# BareBones-Arduino.net
KiCad netlist of a schematic drawn in EAGLE
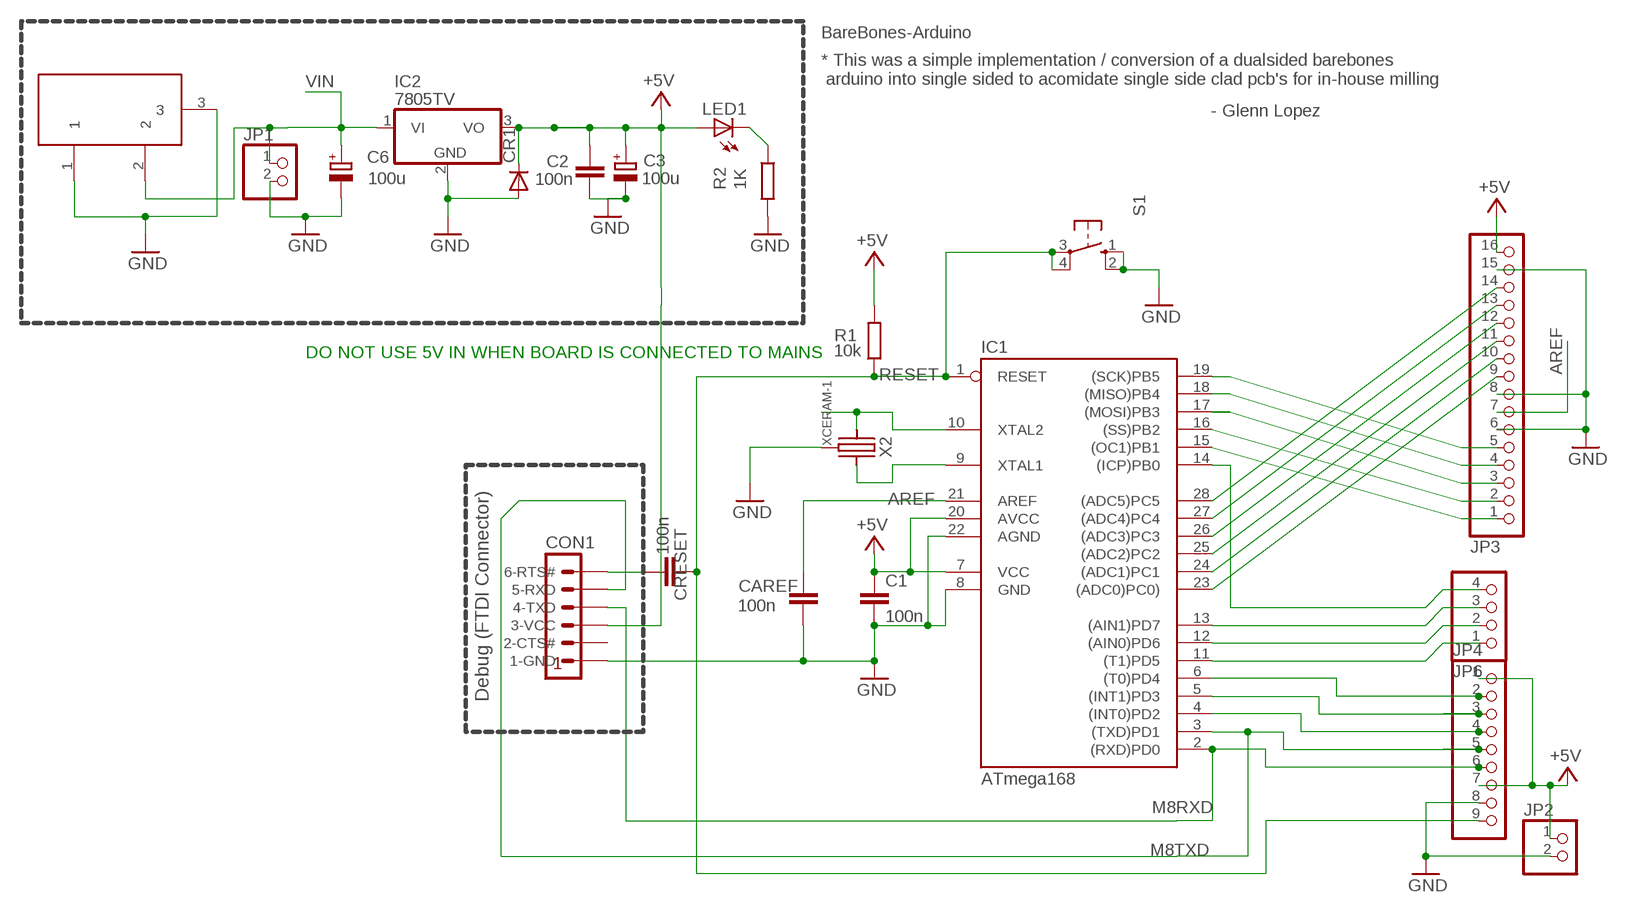
[diagram p0: schematic, sheet 1]

(export (version "E")
  (design (tool "Eeschema 10.0.6"))
  (components
    (comp (ref "C1")
      (value "100n")
      (footprint "eagle-import:C025-025X050")
      (libsource (lib "eagle-import") (part "C-EU025-025X050"))
    )
    (comp (ref "C2")
      (value "100n")
      (footprint "eagle-import:C1206K")
      (libsource (lib "eagle-import") (part "C-EUC1206K"))
    )
    (comp (ref "C3")
      (value "100u")
      (footprint "eagle-import:E2,5-7")
      (libsource (lib "eagle-import") (part "CPOL-EUE2.5-7"))
    )
    (comp (ref "C6")
      (value "100u")
      (footprint "eagle-import:E2,5-7")
      (libsource (lib "eagle-import") (part "CPOL-EUE2.5-7"))
    )
    (comp (ref "CAREF")
      (value "100n")
      (footprint "eagle-import:C1206K")
      (libsource (lib "eagle-import") (part "C-EUC1206K"))
    )
    (comp (ref "CON1")
      (value "FTDI-TTL232R")
      (footprint "eagle-import:MA06-1")
      (libsource (lib "eagle-import") (part "FTDI-TTL232R"))
    )
    (comp (ref "CR1")
      (value "DIODE-1ARECT-2V")
      (footprint "eagle-import:DO41-2V")
      (libsource (lib "eagle-import") (part "DIODE-1ARECT-2V"))
    )
    (comp (ref "CRESET")
      (value "100n")
      (footprint "eagle-import:C025-025X050")
      (libsource (lib "eagle-import") (part "C-EU025-025X050"))
    )
    (comp (ref "IC1")
      (value "ATmega168")
      (footprint "eagle-import:DIL28-3")
      (libsource (lib "eagle-import") (part "AT90S4433P"))
    )
    (comp (ref "IC2")
      (value "7805TV")
      (footprint "eagle-import:TO220V")
      (libsource (lib "eagle-import") (part "78TV05"))
    )
    (comp (ref "JP1")
      (value "PINHD-1X2")
      (footprint "eagle-import:1X02")
      (libsource (lib "eagle-import") (part "PINHD-1X2"))
    )
    (comp (ref "JP2")
      (value "PINHD-1X2")
      (footprint "eagle-import:1X02")
      (libsource (lib "eagle-import") (part "PINHD-1X2"))
    )
    (comp (ref "JP3")
      (value "PINHD-1X16-BARE")
      (footprint "eagle-import:1X16-BARE")
      (libsource (lib "eagle-import") (part "PINHD-1X16-BARE"))
    )
    (comp (ref "JP4")
      (value "PINHD-1X9-BARE")
      (footprint "eagle-import:1X09-BARE")
      (libsource (lib "eagle-import") (part "PINHD-1X9-BARE"))
    )
    (comp (ref "JP6")
      (value "PINHD-1X4-BARE")
      (footprint "eagle-import:1X04-BARE")
      (libsource (lib "eagle-import") (part "PINHD-1X4-BARE"))
    )
    (comp (ref "LED1")
      (value "LED3MM")
      (footprint "eagle-import:LED3MM")
      (libsource (lib "eagle-import") (part "LED3MM"))
    )
    (comp (ref "R1")
      (value "10k")
      (footprint "eagle-import:0204_5")
      (libsource (lib "eagle-import") (part "R-EU_0204/5"))
    )
    (comp (ref "R2")
      (value "1K")
      (footprint "eagle-import:0204_5")
      (libsource (lib "eagle-import") (part "R-EU_0204/5"))
    )
    (comp (ref "S1")
      (value "10-XX")
      (footprint "eagle-import:B3F-10XX")
      (libsource (lib "eagle-import") (part "10-XX"))
    )
    (comp (ref "X2")
      (value "XCERAM-1")
      (footprint "eagle-import:XTAL-3")
      (libsource (lib "eagle-import") (part "XCERAM-1"))
    )
    (comp (ref "X3")
      (value "DC-In")
      (footprint "eagle-import:4UCON-POWER-JACK")
      (libsource (lib "eagle-import") (part "POWERSUPPLY_DC21MM4UCON"))
    )
  )
  (nets
    (net (code "1") (name "+5V") (class "Default")
      (node (ref "C1") (pin "1") (pinfunction "1_1") (pintype "passive"))
      (node (ref "C2") (pin "2") (pinfunction "2_2") (pintype "passive"))
      (node (ref "C3") (pin "+") (pinfunction "+_+") (pintype "passive"))
      (node (ref "CON1") (pin "3") (pinfunction "3-VCC_3") (pintype "passive"))
      (node (ref "CR1") (pin "C") (pinfunction "C_C") (pintype "passive"))
      (node (ref "IC1") (pin "20") (pinfunction "AVCC_20") (pintype "power_in"))
      (node (ref "IC1") (pin "7") (pinfunction "VCC_7") (pintype "power_in"))
      (node (ref "IC2") (pin "3") (pinfunction "VO_3") (pintype "passive"))
      (node (ref "JP2") (pin "1") (pinfunction "1_1") (pintype "passive"))
      (node (ref "JP3") (pin "16") (pinfunction "16_16") (pintype "passive"))
      (node (ref "JP4") (pin "1") (pinfunction "1_1") (pintype "passive"))
      (node (ref "JP4") (pin "7") (pinfunction "7_7") (pintype "passive"))
      (node (ref "LED1") (pin "A") (pinfunction "A_A") (pintype "passive"))
      (node (ref "R1") (pin "2") (pinfunction "2_2") (pintype "passive"))
    )
    (net (code "2") (name "/AREF") (class "Default")
      (node (ref "CAREF") (pin "2") (pinfunction "2_2") (pintype "passive"))
      (node (ref "IC1") (pin "21") (pinfunction "AREF_21") (pintype "passive"))
      (node (ref "JP3") (pin "7") (pinfunction "7_7") (pintype "passive"))
    )
    (net (code "3") (name "/M8RXD") (class "Default")
      (node (ref "CON1") (pin "4") (pinfunction "4-TXD_4") (pintype "passive"))
      (node (ref "IC1") (pin "2") (pinfunction "(RXD)PD0_2") (pintype "bidirectional"))
      (node (ref "JP4") (pin "6") (pinfunction "6_6") (pintype "passive"))
    )
    (net (code "4") (name "/M8TXD") (class "Default")
      (node (ref "CON1") (pin "5") (pinfunction "5-RXD_5") (pintype "passive"))
      (node (ref "IC1") (pin "3") (pinfunction "(TXD)PD1_3") (pintype "bidirectional"))
      (node (ref "JP4") (pin "5") (pinfunction "5_5") (pintype "passive"))
    )
    (net (code "5") (name "/RESET") (class "Default")
      (node (ref "CRESET") (pin "2") (pinfunction "2_2") (pintype "passive"))
      (node (ref "IC1") (pin "1") (pinfunction "RESET_1") (pintype "input"))
      (node (ref "JP4") (pin "9") (pinfunction "9_9") (pintype "passive"))
      (node (ref "R1") (pin "1") (pinfunction "1_1") (pintype "passive"))
      (node (ref "S1") (pin "3") (pinfunction "P_3") (pintype "passive"))
      (node (ref "S1") (pin "4") (pinfunction "P1_4") (pintype "passive"))
    )
    (net (code "6") (name "/VIN") (class "Default")
      (node (ref "C6") (pin "+") (pinfunction "+_+") (pintype "passive"))
      (node (ref "IC2") (pin "1") (pinfunction "VI_1") (pintype "input"))
      (node (ref "JP1") (pin "1") (pinfunction "1_1") (pintype "passive"))
      (node (ref "X3") (pin "2") (pinfunction "2_2") (pintype "passive"))
    )
    (net (code "7") (name "GND") (class "Default")
      (node (ref "C1") (pin "2") (pinfunction "2_2") (pintype "passive"))
      (node (ref "C2") (pin "1") (pinfunction "1_1") (pintype "passive"))
      (node (ref "C3") (pin "-") (pinfunction "-_-") (pintype "passive"))
      (node (ref "C6") (pin "-") (pinfunction "-_-") (pintype "passive"))
      (node (ref "CAREF") (pin "1") (pinfunction "1_1") (pintype "passive"))
      (node (ref "CON1") (pin "1") (pinfunction "1-GND_1") (pintype "passive"))
      (node (ref "CR1") (pin "A") (pinfunction "A_A") (pintype "passive"))
      (node (ref "IC1") (pin "22") (pinfunction "AGND_22") (pintype "power_in"))
      (node (ref "IC1") (pin "8") (pinfunction "GND_8") (pintype "power_in"))
      (node (ref "IC2") (pin "2") (pinfunction "GND_2") (pintype "passive"))
      (node (ref "JP1") (pin "2") (pinfunction "2_2") (pintype "passive"))
      (node (ref "JP2") (pin "2") (pinfunction "2_2") (pintype "passive"))
      (node (ref "JP3") (pin "15") (pinfunction "15_15") (pintype "passive"))
      (node (ref "JP3") (pin "6") (pinfunction "6_6") (pintype "passive"))
      (node (ref "JP3") (pin "8") (pinfunction "8_8") (pintype "passive"))
      (node (ref "JP4") (pin "8") (pinfunction "8_8") (pintype "passive"))
      (node (ref "R2") (pin "2") (pinfunction "2_2") (pintype "passive"))
      (node (ref "S1") (pin "1") (pinfunction "S_1") (pintype "passive"))
      (node (ref "S1") (pin "2") (pinfunction "S1_2") (pintype "passive"))
      (node (ref "X2") (pin "P$2") (pinfunction "GND_P$2") (pintype "passive"))
      (node (ref "X3") (pin "1") (pinfunction "1_1") (pintype "passive"))
      (node (ref "X3") (pin "3") (pinfunction "3_3") (pintype "passive"))
    )
    (net (code "8") (name "Net-(CON1-6-RTS#)") (class "Default")
      (node (ref "CON1") (pin "6") (pinfunction "6-RTS#_6") (pintype "passive"))
      (node (ref "CRESET") (pin "1") (pinfunction "1_1") (pintype "passive"))
    )
    (net (code "9") (name "Net-(IC1-(ADC0)PC0))") (class "Default")
      (node (ref "IC1") (pin "23") (pinfunction "(ADC0)PC0)_23") (pintype "bidirectional"))
      (node (ref "JP3") (pin "9") (pinfunction "9_9") (pintype "passive"))
    )
    (net (code "10") (name "Net-(IC1-(ADC1)PC1)") (class "Default")
      (node (ref "IC1") (pin "24") (pinfunction "(ADC1)PC1_24") (pintype "bidirectional"))
      (node (ref "JP3") (pin "10") (pinfunction "10_10") (pintype "passive"))
    )
    (net (code "11") (name "Net-(IC1-(ADC2)PC2)") (class "Default")
      (node (ref "IC1") (pin "25") (pinfunction "(ADC2)PC2_25") (pintype "bidirectional"))
      (node (ref "JP3") (pin "11") (pinfunction "11_11") (pintype "passive"))
    )
    (net (code "12") (name "Net-(IC1-(ADC3)PC3)") (class "Default")
      (node (ref "IC1") (pin "26") (pinfunction "(ADC3)PC3_26") (pintype "bidirectional"))
      (node (ref "JP3") (pin "12") (pinfunction "12_12") (pintype "passive"))
    )
    (net (code "13") (name "Net-(IC1-(ADC4)PC4)") (class "Default")
      (node (ref "IC1") (pin "27") (pinfunction "(ADC4)PC4_27") (pintype "bidirectional"))
      (node (ref "JP3") (pin "13") (pinfunction "13_13") (pintype "passive"))
    )
    (net (code "14") (name "Net-(IC1-(ADC5)PC5)") (class "Default")
      (node (ref "IC1") (pin "28") (pinfunction "(ADC5)PC5_28") (pintype "bidirectional"))
      (node (ref "JP3") (pin "14") (pinfunction "14_14") (pintype "passive"))
    )
    (net (code "15") (name "Net-(IC1-(AIN0)PD6)") (class "Default")
      (node (ref "IC1") (pin "12") (pinfunction "(AIN0)PD6_12") (pintype "bidirectional"))
      (node (ref "JP6") (pin "2") (pinfunction "2_2") (pintype "passive"))
    )
    (net (code "16") (name "Net-(IC1-(AIN1)PD7)") (class "Default")
      (node (ref "IC1") (pin "13") (pinfunction "(AIN1)PD7_13") (pintype "bidirectional"))
      (node (ref "JP6") (pin "3") (pinfunction "3_3") (pintype "passive"))
    )
    (net (code "17") (name "Net-(IC1-(ICP)PB0)") (class "Default")
      (node (ref "IC1") (pin "14") (pinfunction "(ICP)PB0_14") (pintype "bidirectional"))
      (node (ref "JP6") (pin "4") (pinfunction "4_4") (pintype "passive"))
    )
    (net (code "18") (name "Net-(IC1-(INT0)PD2)") (class "Default")
      (node (ref "IC1") (pin "4") (pinfunction "(INT0)PD2_4") (pintype "bidirectional"))
      (node (ref "JP4") (pin "4") (pinfunction "4_4") (pintype "passive"))
    )
    (net (code "19") (name "Net-(IC1-(INT1)PD3)") (class "Default")
      (node (ref "IC1") (pin "5") (pinfunction "(INT1)PD3_5") (pintype "bidirectional"))
      (node (ref "JP4") (pin "3") (pinfunction "3_3") (pintype "passive"))
    )
    (net (code "20") (name "Net-(IC1-(MISO)PB4)") (class "Default")
      (node (ref "IC1") (pin "18") (pinfunction "(MISO)PB4_18") (pintype "bidirectional"))
      (node (ref "JP3") (pin "4") (pinfunction "4_4") (pintype "passive"))
    )
    (net (code "21") (name "Net-(IC1-(MOSI)PB3)") (class "Default")
      (node (ref "IC1") (pin "17") (pinfunction "(MOSI)PB3_17") (pintype "bidirectional"))
      (node (ref "JP3") (pin "3") (pinfunction "3_3") (pintype "passive"))
    )
    (net (code "22") (name "Net-(IC1-(OC1)PB1)") (class "Default")
      (node (ref "IC1") (pin "15") (pinfunction "(OC1)PB1_15") (pintype "bidirectional"))
      (node (ref "JP3") (pin "1") (pinfunction "1_1") (pintype "passive"))
    )
    (net (code "23") (name "Net-(IC1-(SCK)PB5)") (class "Default")
      (node (ref "IC1") (pin "19") (pinfunction "(SCK)PB5_19") (pintype "bidirectional"))
      (node (ref "JP3") (pin "5") (pinfunction "5_5") (pintype "passive"))
    )
    (net (code "24") (name "Net-(IC1-(SS)PB2)") (class "Default")
      (node (ref "IC1") (pin "16") (pinfunction "(SS)PB2_16") (pintype "bidirectional"))
      (node (ref "JP3") (pin "2") (pinfunction "2_2") (pintype "passive"))
    )
    (net (code "25") (name "Net-(IC1-(T0)PD4)") (class "Default")
      (node (ref "IC1") (pin "6") (pinfunction "(T0)PD4_6") (pintype "bidirectional"))
      (node (ref "JP4") (pin "2") (pinfunction "2_2") (pintype "passive"))
    )
    (net (code "26") (name "Net-(IC1-(T1)PD5)") (class "Default")
      (node (ref "IC1") (pin "11") (pinfunction "(T1)PD5_11") (pintype "bidirectional"))
      (node (ref "JP6") (pin "1") (pinfunction "1_1") (pintype "passive"))
    )
    (net (code "27") (name "Net-(IC1-XTAL1)") (class "Default")
      (node (ref "IC1") (pin "9") (pinfunction "XTAL1_9") (pintype "bidirectional"))
      (node (ref "X2") (pin "P$3") (pinfunction "P$1_P$3") (pintype "passive"))
    )
    (net (code "28") (name "Net-(IC1-XTAL2)") (class "Default")
      (node (ref "IC1") (pin "10") (pinfunction "XTAL2_10") (pintype "bidirectional"))
      (node (ref "X2") (pin "P$1") (pinfunction "P$2_P$1") (pintype "passive"))
    )
    (net (code "29") (name "Net-(LED1-C)") (class "Default")
      (node (ref "LED1") (pin "K") (pinfunction "C_K") (pintype "passive"))
      (node (ref "R2") (pin "1") (pinfunction "1_1") (pintype "passive"))
    )
    (net (code "30") (name "unconnected-(CON1-2-CTS#-Pad2)") (class "Default")
      (node (ref "CON1") (pin "2") (pinfunction "2-CTS#_2") (pintype "passive"))
    )
  )
)
